# URA.net
KiCad netlist of a schematic drawn in EAGLE
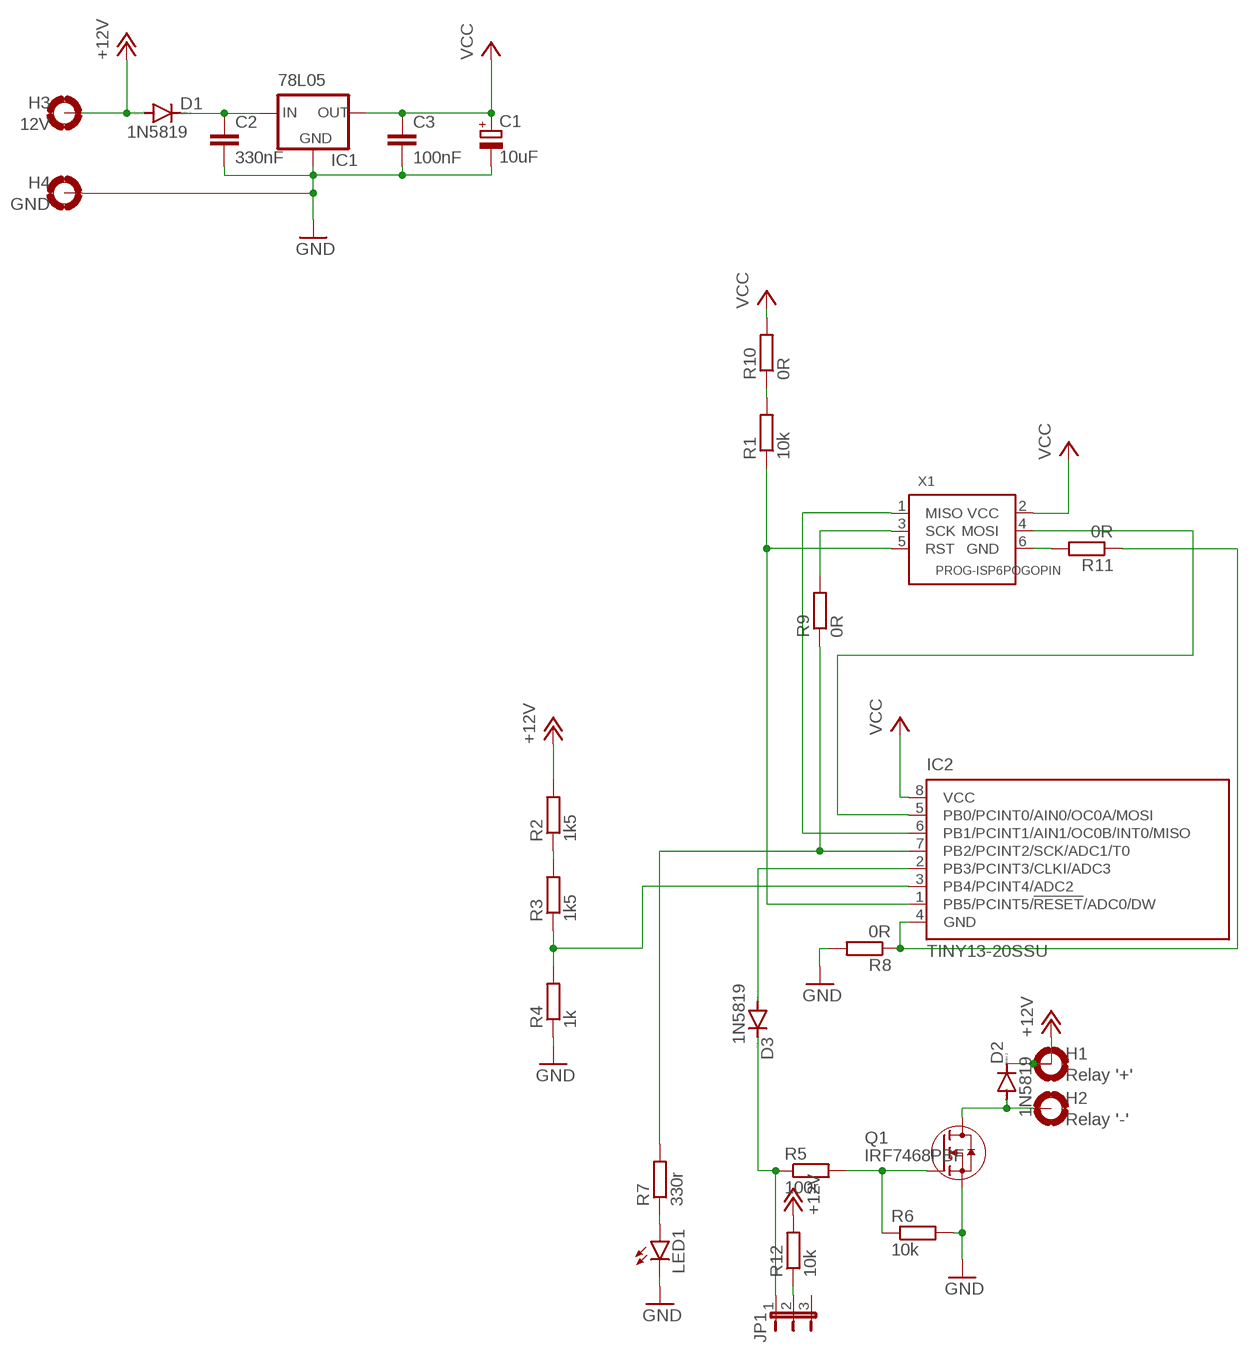
[diagram p0: schematic, sheet 1]

(export (version "E")
  (design (tool "Eeschema 10.0.6"))
  (components
    (comp (ref "C1")
      (value "10uF")
      (footprint "eagle-import:CT3216")
      (libsource (lib "eagle-import") (part "CPOL-EUCT3216"))
    )
    (comp (ref "C2")
      (value "330nF")
      (footprint "eagle-import:C0805K")
      (libsource (lib "eagle-import") (part "C-EUC0805K"))
    )
    (comp (ref "C3")
      (value "100nF")
      (footprint "eagle-import:C0805K")
      (libsource (lib "eagle-import") (part "C-EUC0805K"))
    )
    (comp (ref "D1")
      (value "1N5819")
      (footprint "eagle-import:SOD-123_MINI-SMA")
      (libsource (lib "eagle-import") (part "CGRM400-G1"))
    )
    (comp (ref "D2")
      (value "1N5819")
      (footprint "eagle-import:SOD-123_MINI-SMA")
      (libsource (lib "eagle-import") (part "CGRM400-G1"))
    )
    (comp (ref "D3")
      (value "1N5819")
      (footprint "eagle-import:SOD-123_MINI-SMA")
      (libsource (lib "eagle-import") (part "CGRM400-G1"))
    )
    (comp (ref "H1")
      (value "Relay '+'")
      (footprint "eagle-import:2,8-PAD")
      (libsource (lib "eagle-import") (part "MOUNT-PAD-ROUND2.8"))
    )
    (comp (ref "H2")
      (value "Relay '-'")
      (footprint "eagle-import:2,8-PAD")
      (libsource (lib "eagle-import") (part "MOUNT-PAD-ROUND2.8"))
    )
    (comp (ref "H3")
      (value "12V")
      (footprint "eagle-import:2,8-PAD")
      (libsource (lib "eagle-import") (part "MOUNT-PAD-ROUND2.8"))
    )
    (comp (ref "H4")
      (value "GND")
      (footprint "eagle-import:2,8-PAD")
      (libsource (lib "eagle-import") (part "MOUNT-PAD-ROUND2.8"))
    )
    (comp (ref "IC1")
      (value "78L05")
      (footprint "eagle-import:78LXX-SOT89")
      (libsource (lib "eagle-import") (part "78LXXSOT89"))
    )
    (comp (ref "IC2")
      (value "TINY13-20SSU")
      (footprint "eagle-import:8S1")
      (fields (field (name "MPN") "ATTINY13-20SSU"))
      (libsource (lib "eagle-import") (part "TINY13SSU-20"))
    )
    (comp (ref "JP1")
      (value "JP2E")
      (footprint "eagle-import:JP2")
      (libsource (lib "eagle-import") (part "JP2E"))
    )
    (comp (ref "LED1")
      (value "LEDCHIP-LED0805")
      (footprint "eagle-import:CHIP-LED0805")
      (libsource (lib "eagle-import") (part "LEDCHIP-LED0805"))
    )
    (comp (ref "Q1")
      (value "IRF7468PBF")
      (footprint "eagle-import:SO08")
      (libsource (lib "eagle-import") (part "IRF7468PBF"))
    )
    (comp (ref "R1")
      (value "10k")
      (footprint "eagle-import:R0805")
      (libsource (lib "eagle-import") (part "R-EU_R0805"))
    )
    (comp (ref "R2")
      (value "1k5")
      (footprint "eagle-import:R0805")
      (libsource (lib "eagle-import") (part "R-EU_R0805"))
    )
    (comp (ref "R3")
      (value "1k5")
      (footprint "eagle-import:R0805")
      (libsource (lib "eagle-import") (part "R-EU_R0805"))
    )
    (comp (ref "R4")
      (value "1k")
      (footprint "eagle-import:R0805")
      (libsource (lib "eagle-import") (part "R-EU_R0805"))
    )
    (comp (ref "R5")
      (value "100r")
      (footprint "eagle-import:R0805")
      (libsource (lib "eagle-import") (part "R-EU_R0805"))
    )
    (comp (ref "R6")
      (value "10k")
      (footprint "eagle-import:R0805")
      (libsource (lib "eagle-import") (part "R-EU_R0805"))
    )
    (comp (ref "R7")
      (value "330r")
      (footprint "eagle-import:R0805")
      (libsource (lib "eagle-import") (part "R-EU_R0805"))
    )
    (comp (ref "R8")
      (value "0R")
      (footprint "eagle-import:R1206")
      (libsource (lib "eagle-import") (part "R0_1206"))
    )
    (comp (ref "R9")
      (value "0R")
      (footprint "eagle-import:R1206")
      (libsource (lib "eagle-import") (part "R0_1206"))
    )
    (comp (ref "R10")
      (value "0R")
      (footprint "eagle-import:R1206")
      (libsource (lib "eagle-import") (part "R0_1206"))
    )
    (comp (ref "R11")
      (value "0R")
      (footprint "eagle-import:R1206")
      (libsource (lib "eagle-import") (part "R0_1206"))
    )
    (comp (ref "R12")
      (value "10k")
      (footprint "eagle-import:R0805")
      (libsource (lib "eagle-import") (part "R-EU_R0805"))
    )
    (comp (ref "X1")
      (value "PROG-ISP6POGOPIN")
      (footprint "eagle-import:PROG_POGOPIN")
      (libsource (lib "eagle-import") (part "PROG-ISP6POGOPIN"))
    )
  )
  (nets
    (net (code "1") (name "+12V") (class "Default")
      (node (ref "D1") (pin "A") (pinfunction "A_A") (pintype "passive"))
      (node (ref "D2") (pin "C") (pinfunction "C_C") (pintype "passive"))
      (node (ref "H1") (pin "B2,8") (pinfunction "MOUNT_B2,8") (pintype "passive"))
      (node (ref "H3") (pin "B2,8") (pinfunction "MOUNT_B2,8") (pintype "passive"))
      (node (ref "R12") (pin "2") (pinfunction "2_2") (pintype "passive"))
      (node (ref "R2") (pin "2") (pinfunction "2_2") (pintype "passive"))
    )
    (net (code "2") (name "GND") (class "Default")
      (node (ref "C1") (pin "-") (pinfunction "-_-") (pintype "passive"))
      (node (ref "C2") (pin "2") (pinfunction "2_2") (pintype "passive"))
      (node (ref "C3") (pin "2") (pinfunction "2_2") (pintype "passive"))
      (node (ref "H4") (pin "B2,8") (pinfunction "MOUNT_B2,8") (pintype "passive"))
      (node (ref "IC1") (pin "GND@0") (pinfunction "GND_GND@0") (pintype "input"))
      (node (ref "IC1") (pin "GND@1") (pinfunction "GND_GND@1") (pintype "input"))
      (node (ref "LED1") (pin "C") (pinfunction "C_C") (pintype "passive"))
      (node (ref "Q1") (pin "1") (pinfunction "S_1") (pintype "passive"))
      (node (ref "Q1") (pin "2") (pinfunction "S_2") (pintype "passive"))
      (node (ref "Q1") (pin "3") (pinfunction "S_3") (pintype "passive"))
      (node (ref "R4") (pin "1") (pinfunction "1_1") (pintype "passive"))
      (node (ref "R6") (pin "2") (pinfunction "2_2") (pintype "passive"))
      (node (ref "R8") (pin "2") (pinfunction "2_2") (pintype "passive"))
    )
    (net (code "3") (name "Net-(C2-Pad1)") (class "Default")
      (node (ref "C2") (pin "1") (pinfunction "1_1") (pintype "passive"))
      (node (ref "D1") (pin "C") (pinfunction "C_C") (pintype "passive"))
      (node (ref "IC1") (pin "IN") (pinfunction "IN_IN") (pintype "input"))
    )
    (net (code "4") (name "Net-(D3-PadC)") (class "Default")
      (node (ref "D3") (pin "C") (pinfunction "C_C") (pintype "passive"))
      (node (ref "JP1") (pin "1") (pinfunction "1_1") (pintype "passive"))
      (node (ref "R5") (pin "1") (pinfunction "1_1") (pintype "passive"))
    )
    (net (code "5") (name "Net-(H2-MOUNT)") (class "Default")
      (node (ref "D2") (pin "A") (pinfunction "A_A") (pintype "passive"))
      (node (ref "H2") (pin "B2,8") (pinfunction "MOUNT_B2,8") (pintype "passive"))
      (node (ref "Q1") (pin "5") (pinfunction "D_5") (pintype "passive"))
      (node (ref "Q1") (pin "6") (pinfunction "D_6") (pintype "passive"))
      (node (ref "Q1") (pin "7") (pinfunction "D_7") (pintype "passive"))
      (node (ref "Q1") (pin "8") (pinfunction "D_8") (pintype "passive"))
    )
    (net (code "6") (name "Net-(IC2-GND)") (class "Default")
      (node (ref "IC2") (pin "4") (pinfunction "GND_4") (pintype "power_in"))
      (node (ref "R11") (pin "1") (pinfunction "1_1") (pintype "passive"))
      (node (ref "R8") (pin "1") (pinfunction "1_1") (pintype "passive"))
    )
    (net (code "7") (name "Net-(IC2-PB0{slash}PCINT0{slash}AIN0{slash}OC0A{slash}MOSI)") (class "Default")
      (node (ref "IC2") (pin "5") (pinfunction "PB0/PCINT0/AIN0/OC0A/MOSI_5") (pintype "bidirectional"))
      (node (ref "X1") (pin "4") (pinfunction "MOSI_4") (pintype "bidirectional"))
    )
    (net (code "8") (name "Net-(IC2-PB1{slash}PCINT1{slash}AIN1{slash}OC0B{slash}INT0{slash}MISO)") (class "Default")
      (node (ref "IC2") (pin "6") (pinfunction "PB1/PCINT1/AIN1/OC0B/INT0/MISO_6") (pintype "bidirectional"))
      (node (ref "X1") (pin "1") (pinfunction "MISO_1") (pintype "bidirectional"))
    )
    (net (code "9") (name "Net-(IC2-PB2{slash}PCINT2{slash}SCK{slash}ADC1{slash}T0)") (class "Default")
      (node (ref "IC2") (pin "7") (pinfunction "PB2/PCINT2/SCK/ADC1/T0_7") (pintype "bidirectional"))
      (node (ref "R7") (pin "2") (pinfunction "2_2") (pintype "passive"))
      (node (ref "R9") (pin "1") (pinfunction "1_1") (pintype "passive"))
    )
    (net (code "10") (name "Net-(IC2-PB3{slash}PCINT3{slash}CLKI{slash}ADC3)") (class "Default")
      (node (ref "D3") (pin "A") (pinfunction "A_A") (pintype "passive"))
      (node (ref "IC2") (pin "2") (pinfunction "PB3/PCINT3/CLKI/ADC3_2") (pintype "bidirectional"))
    )
    (net (code "11") (name "Net-(IC2-PB4{slash}PCINT4{slash}ADC2)") (class "Default")
      (node (ref "IC2") (pin "3") (pinfunction "PB4/PCINT4/ADC2_3") (pintype "bidirectional"))
      (node (ref "R3") (pin "1") (pinfunction "1_1") (pintype "passive"))
      (node (ref "R4") (pin "2") (pinfunction "2_2") (pintype "passive"))
    )
    (net (code "12") (name "Net-(IC2-PB5{slash}PCINT5{slash}~{RESET}{slash}ADC0{slash}DW)") (class "Default")
      (node (ref "IC2") (pin "1") (pinfunction "PB5/PCINT5/~{RESET}/ADC0/DW_1") (pintype "bidirectional"))
      (node (ref "R1") (pin "1") (pinfunction "1_1") (pintype "passive"))
      (node (ref "X1") (pin "5") (pinfunction "RST_5") (pintype "bidirectional"))
    )
    (net (code "13") (name "Net-(JP1-Pad2)") (class "Default")
      (node (ref "JP1") (pin "2") (pinfunction "2_2") (pintype "passive"))
      (node (ref "R12") (pin "1") (pinfunction "1_1") (pintype "passive"))
    )
    (net (code "14") (name "Net-(LED1-PadA)") (class "Default")
      (node (ref "LED1") (pin "A") (pinfunction "A_A") (pintype "passive"))
      (node (ref "R7") (pin "1") (pinfunction "1_1") (pintype "passive"))
    )
    (net (code "15") (name "Net-(Q1-G)") (class "Default")
      (node (ref "Q1") (pin "4") (pinfunction "G_4") (pintype "passive"))
      (node (ref "R5") (pin "2") (pinfunction "2_2") (pintype "passive"))
      (node (ref "R6") (pin "1") (pinfunction "1_1") (pintype "passive"))
    )
    (net (code "16") (name "Net-(R1-Pad2)") (class "Default")
      (node (ref "R1") (pin "2") (pinfunction "2_2") (pintype "passive"))
      (node (ref "R10") (pin "1") (pinfunction "1_1") (pintype "passive"))
    )
    (net (code "17") (name "Net-(R2-Pad1)") (class "Default")
      (node (ref "R2") (pin "1") (pinfunction "1_1") (pintype "passive"))
      (node (ref "R3") (pin "2") (pinfunction "2_2") (pintype "passive"))
    )
    (net (code "18") (name "Net-(X1-GND)") (class "Default")
      (node (ref "R11") (pin "2") (pinfunction "2_2") (pintype "passive"))
      (node (ref "X1") (pin "6") (pinfunction "GND_6") (pintype "power_in"))
    )
    (net (code "19") (name "Net-(X1-SCK)") (class "Default")
      (node (ref "R9") (pin "2") (pinfunction "2_2") (pintype "passive"))
      (node (ref "X1") (pin "3") (pinfunction "SCK_3") (pintype "bidirectional"))
    )
    (net (code "20") (name "VCC") (class "Default")
      (node (ref "C1") (pin "+") (pinfunction "+_+") (pintype "passive"))
      (node (ref "C3") (pin "1") (pinfunction "1_1") (pintype "passive"))
      (node (ref "IC1") (pin "OUT") (pinfunction "OUT_OUT") (pintype "passive"))
      (node (ref "IC2") (pin "8") (pinfunction "VCC_8") (pintype "power_in"))
      (node (ref "R10") (pin "2") (pinfunction "2_2") (pintype "passive"))
      (node (ref "X1") (pin "2") (pinfunction "VCC_2") (pintype "bidirectional"))
    )
    (net (code "21") (name "unconnected-(JP1-Pad3)") (class "Default")
      (node (ref "JP1") (pin "3") (pinfunction "3_3") (pintype "passive"))
    )
  )
)
